# design.net
KiCad netlist of a schematic drawn in Altium Designer
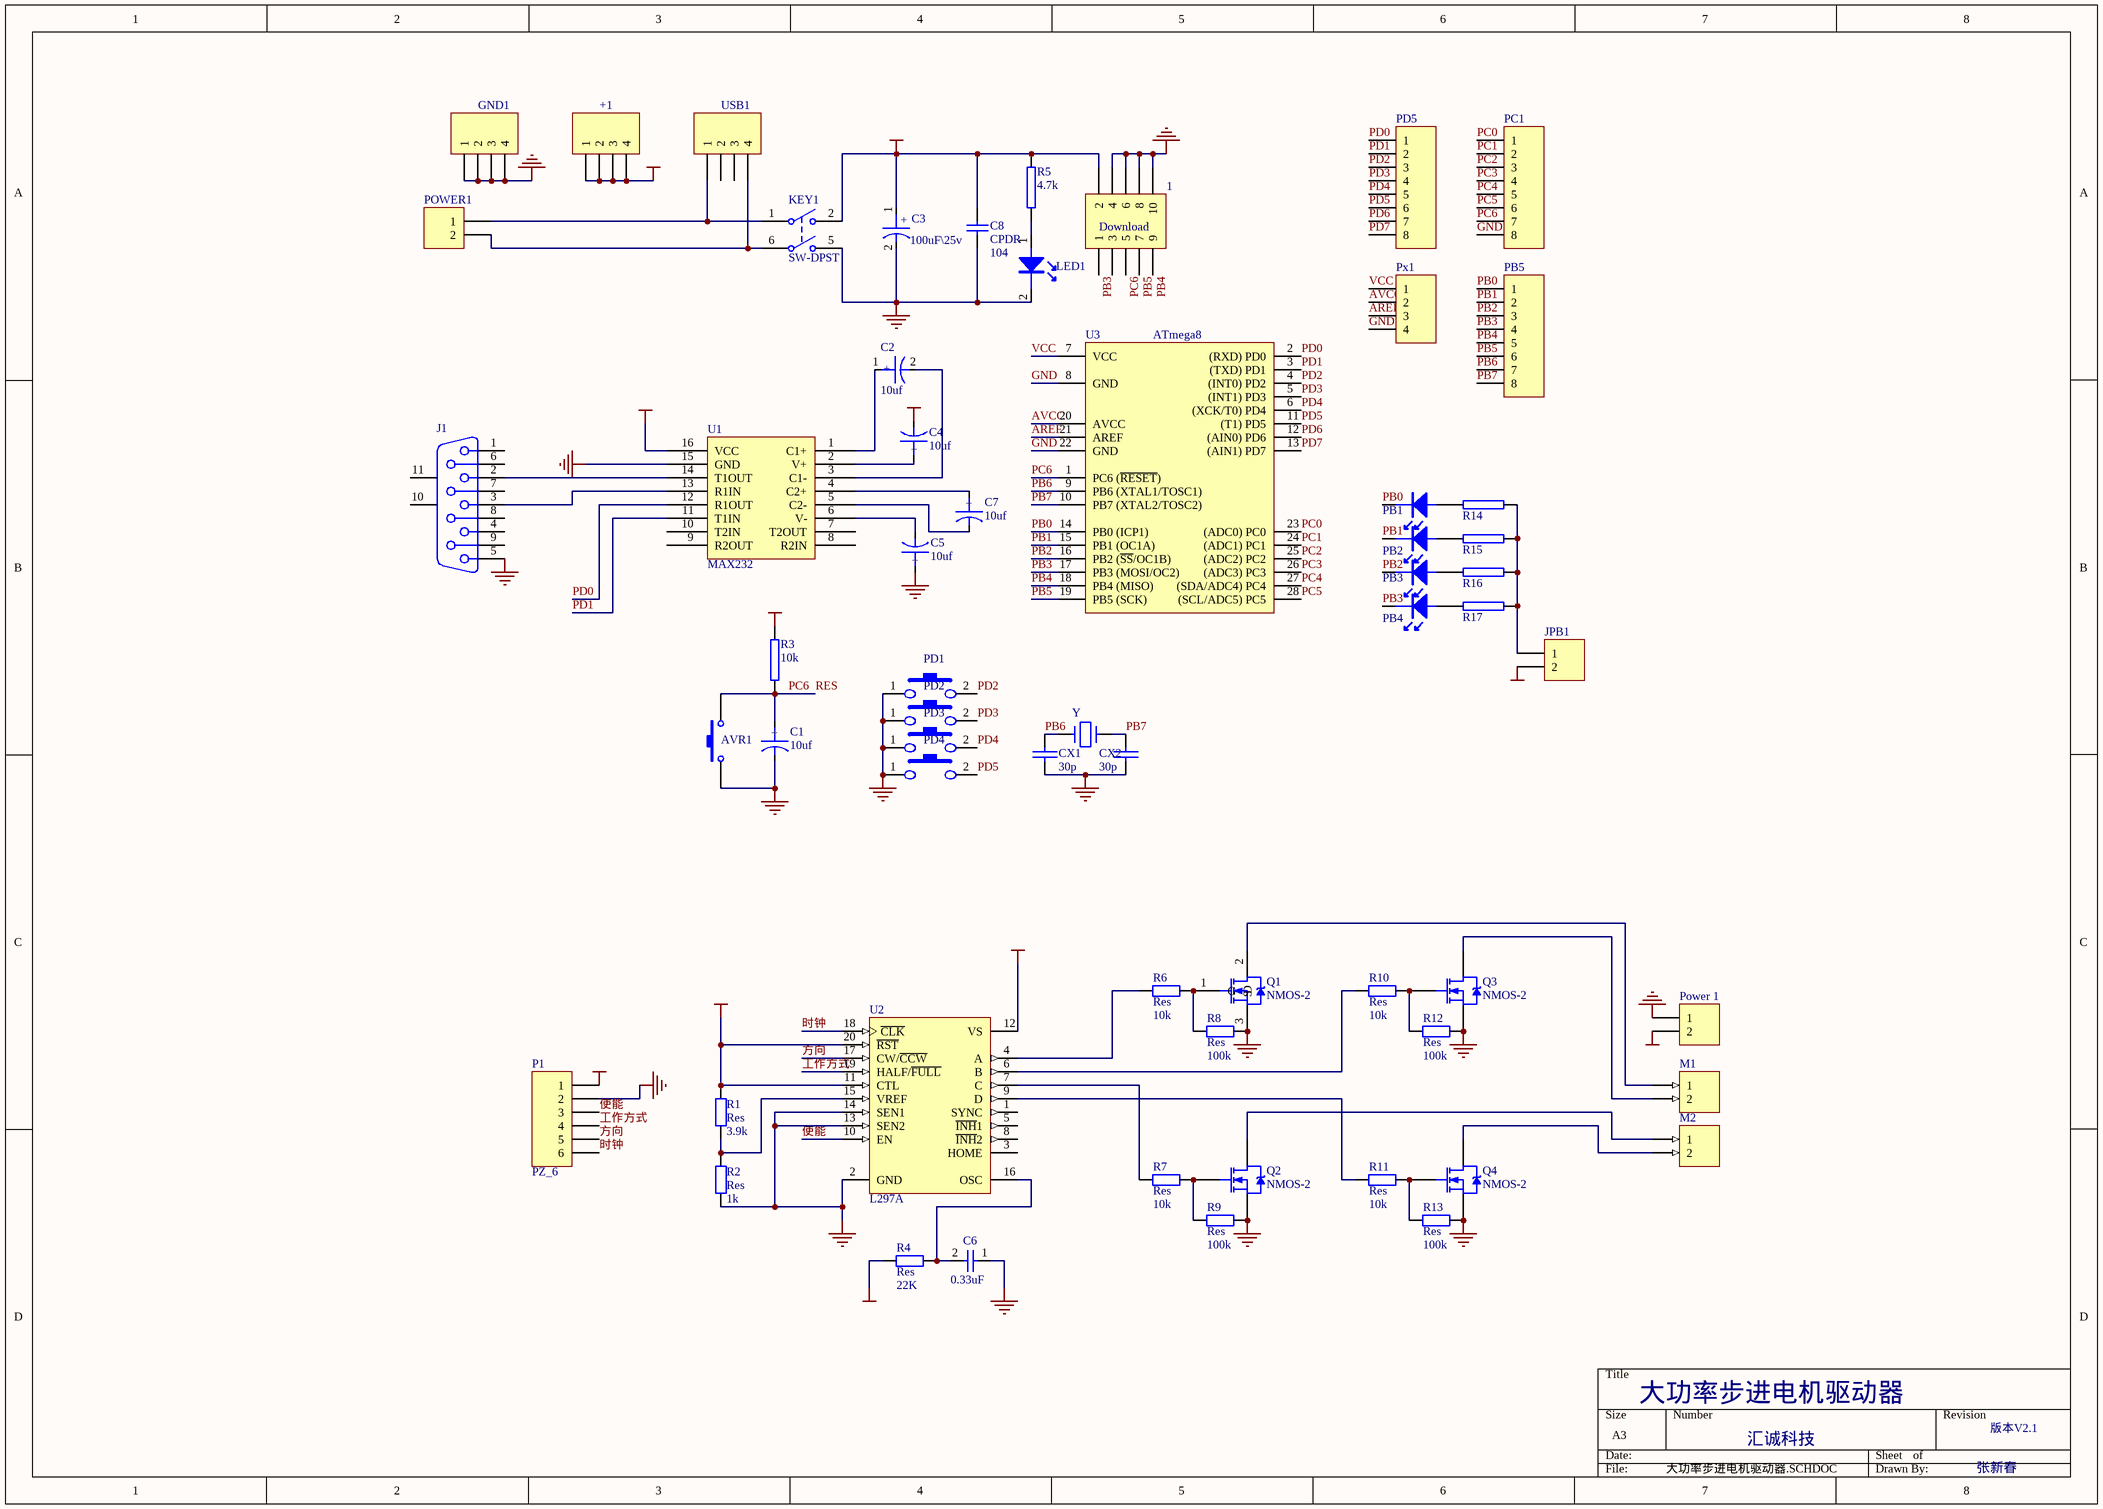
[diagram p0: 大功率步进电机驱动器.SCHDOC]

(export (version "E")
  (design (tool "Eeschema 10.0.6"))
  (components
    (comp (ref "+1")
      (value "~")
      (footprint "HDR1X4")
      (description "Header, 4-Pin")
      (fields (field (name "PUBLISHER") "Altium Limited"))
      (libsource (lib "Miscellaneous Connectors") (part "Header 4"))
    )
    (comp (ref "1")
      (value "Download")
      (footprint "HDR-2x5")
      (description "Header, 5-Pin, Dual row")
      (fields (field (name "PUBLISHER") "Altium Limited"))
      (libsource (lib "Miscellaneous Connectors") (part "Header 5X2"))
    )
    (comp (ref "AVR1")
      (value "~")
      (footprint "an-6*6")
      (description "Switch")
      (fields (field (name "PUBLISHER") "Altium Limited"))
      (libsource (lib "Miscellaneous Devices") (part "SW-PB"))
    )
    (comp (ref "C1")
      (value "10uf")
      (footprint "C-DJ-4")
      (description "Capacitor")
      (libsource (lib "*") (part "CAPACITOR POL"))
    )
    (comp (ref "C2")
      (value "10uf")
      (footprint "C-DJ-4")
      (description "Capacitor")
      (libsource (lib "") (part "CAPACITOR POL_1"))
    )
    (comp (ref "C3")
      (value "100u~{F}25v")
      (footprint "C-DJ-6")
      (description "Capacitor")
      (libsource (lib "OldCow1 (1)") (part "CAPACITOR POL"))
    )
    (comp (ref "C4")
      (value "10uf")
      (footprint "C-DJ-4")
      (description "Capacitor")
      (libsource (lib "*") (part "CAPACITOR POL"))
    )
    (comp (ref "C5")
      (value "10uf")
      (footprint "C-DJ-4")
      (description "Capacitor")
      (libsource (lib "*") (part "CAPACITOR POL"))
    )
    (comp (ref "C6")
      (value "0.33uF")
      (footprint "C-DJ-4")
      (description "Capacitor")
      (fields (field (name "PUBLISHER") "Altium Limited"))
      (libsource (lib "Miscellaneous Devices") (part "Cap"))
    )
    (comp (ref "C7")
      (value "10uf")
      (footprint "C-DJ-4")
      (description "Capacitor")
      (libsource (lib "*") (part "CAPACITOR POL"))
    )
    (comp (ref "C8")
      (value "CPDR")
      (footprint "CPDR")
      (description "瓷片电容")
      (fields (field (name "ALTIUM_VALUE") "104") (field (name "PUBLISHER") "Altium Limited"))
      (libsource (lib "zxcourhc") (part "CPDR"))
    )
    (comp (ref "CX1")
      (value "30p")
      (footprint "HDR1X2")
      (description "Capacitor")
      (libsource (lib "*") (part "CAP"))
    )
    (comp (ref "CX2")
      (value "30p")
      (footprint "HDR1X2")
      (description "Capacitor")
      (libsource (lib "*") (part "CAP"))
    )
    (comp (ref "GND1")
      (value "~")
      (footprint "HDR1X4")
      (description "Header, 4-Pin")
      (fields (field (name "PUBLISHER") "Altium Limited"))
      (libsource (lib "Miscellaneous Connectors") (part "Header 4"))
    )
    (comp (ref "J1")
      (value "D Connector 9")
      (footprint "DSUB1.385-2H9")
      (description "Receptacle Assembly, 9 Position, Right Angle")
      (fields (field (name "PUBLISHER") "Altium Limited"))
      (libsource (lib "Miscellaneous Connectors") (part "D Connector 9"))
    )
    (comp (ref "JPB1")
      (value "~")
      (footprint "HDR1X2")
      (description "Header, 2-Pin")
      (fields (field (name "PUBLISHER") "Altium Limited"))
      (libsource (lib "") (part "Header 2_1"))
    )
    (comp (ref "KEY1")
      (value "SW-DPST")
      (footprint "DPDT-6")
      (description "Double-Pole, Single-Throw Switch")
      (fields (field (name "PUBLISHER") "Altium Limited"))
      (libsource (lib "Miscellaneous Devices") (part "SW-DPST"))
    )
    (comp (ref "LED1") (value "LED") (footprint "LED") (libsource (lib "") (part "LED_1")))
    (comp (ref "M1")
      (value "~")
      (footprint "JK128")
      (description "Header, 2-Pin")
      (fields (field (name "PUBLISHER") "Altium Limited"))
      (libsource (lib "Miscellaneous Connectors") (part "MHDR1X2"))
    )
    (comp (ref "M2")
      (value "~")
      (footprint "JK128")
      (description "Header, 2-Pin")
      (fields (field (name "PUBLISHER") "Altium Limited"))
      (libsource (lib "Miscellaneous Connectors") (part "MHDR1X2"))
    )
    (comp (ref "P1")
      (value "PZ_6")
      (footprint "HDR-6")
      (description "排针——6")
      (fields (field (name "PUBLISHER") "Altium Limited"))
      (libsource (lib "zxcourhc") (part "PZ_6"))
    )
    (comp (ref "PB1") (value "LED") (footprint "HDR1X2") (libsource (lib "OldCow1 (1)") (part "LED")))
    (comp (ref "PB2") (value "LED") (footprint "HDR1X2") (libsource (lib "OldCow1 (1)") (part "LED")))
    (comp (ref "PB3") (value "LED") (footprint "HDR1X2") (libsource (lib "OldCow1 (1)") (part "LED")))
    (comp (ref "PB4") (value "LED") (footprint "HDR1X2") (libsource (lib "OldCow1 (1)") (part "LED")))
    (comp (ref "PB5")
      (value "~")
      (footprint "HDR-8")
      (description "排针——8")
      (fields (field (name "PUBLISHER") "Altium Limited"))
      (libsource (lib "zxcourhc") (part "PZ_8"))
    )
    (comp (ref "PC1")
      (value "~")
      (footprint "HDR-8")
      (description "排针——8")
      (fields (field (name "PUBLISHER") "Altium Limited"))
      (libsource (lib "zxcourhc") (part "PZ_8"))
    )
    (comp (ref "PD1") (value "key1") (footprint "an-6*6") (libsource (lib "OldCow1 (1)") (part "key")))
    (comp (ref "PD2") (value "key2") (footprint "an-6*6") (libsource (lib "OldCow1 (1)") (part "key")))
    (comp (ref "PD3") (value "key3") (footprint "an-6*6") (libsource (lib "OldCow1 (1)") (part "key")))
    (comp (ref "PD4") (value "key4") (footprint "an-6*6") (libsource (lib "OldCow1 (1)") (part "key")))
    (comp (ref "PD5")
      (value "~")
      (footprint "HDR-8")
      (description "排针——8")
      (fields (field (name "PUBLISHER") "Altium Limited"))
      (libsource (lib "zxcourhc") (part "PZ_8"))
    )
    (comp (ref "Power 1")
      (value "~")
      (footprint "JK128")
      (description "Header, 2-Pin")
      (fields (field (name "PUBLISHER") "Altium Limited"))
      (libsource (lib "Miscellaneous Connectors") (part "MHDR1X2"))
    )
    (comp (ref "POWER1")
      (value "~")
      (footprint "JK128")
      (description "Header, 2-Pin")
      (fields (field (name "PUBLISHER") "Altium Limited"))
      (libsource (lib "Miscellaneous Connectors") (part "Header 2"))
    )
    (comp (ref "Px1")
      (value "~")
      (footprint "HDR-4")
      (description "排针——4")
      (fields (field (name "PUBLISHER") "Altium Limited"))
      (libsource (lib "zxcourhc") (part "PZ_4"))
    )
    (comp (ref "Q1")
      (value "NMOS-2")
      (footprint "SFM-T3/A4.7V")
      (description "N-Channel Power MOSFET")
      (fields (field (name "PUBLISHER") "Altium Limited"))
      (libsource (lib "") (part "NMOS-2_1"))
    )
    (comp (ref "Q2")
      (value "NMOS-2")
      (footprint "SFM-T3/A4.7V")
      (description "N-Channel Power MOSFET")
      (fields (field (name "PUBLISHER") "Altium Limited"))
      (libsource (lib "Miscellaneous Devices") (part "NMOS-2"))
    )
    (comp (ref "Q3")
      (value "NMOS-2")
      (footprint "SFM-T3/A4.7V")
      (description "N-Channel Power MOSFET")
      (fields (field (name "PUBLISHER") "Altium Limited"))
      (libsource (lib "Miscellaneous Devices") (part "NMOS-2"))
    )
    (comp (ref "Q4")
      (value "NMOS-2")
      (footprint "SFM-T3/A4.7V")
      (description "N-Channel Power MOSFET")
      (fields (field (name "PUBLISHER") "Altium Limited"))
      (libsource (lib "Miscellaneous Devices") (part "NMOS-2"))
    )
    (comp (ref "R1")
      (value "Res")
      (footprint "zxcourhc:CPDR")
      (description "电阻")
      (fields (field (name "ALTIUM_VALUE") "3.9k") (field (name "PUBLISHER") "Altium Limited"))
      (libsource (lib "") (part "Res_1"))
    )
    (comp (ref "R2")
      (value "Res")
      (footprint "CPDR")
      (description "电阻")
      (fields (field (name "ALTIUM_VALUE") "1k") (field (name "PUBLISHER") "Altium Limited"))
      (libsource (lib "") (part "Res_1"))
    )
    (comp (ref "R3") (value "10k") (footprint "RSE") (libsource (lib "*") (part "RES2")))
    (comp (ref "R4")
      (value "Res")
      (footprint "CPDR")
      (description "电阻")
      (fields (field (name "ALTIUM_VALUE") "22K") (field (name "PUBLISHER") "Altium Limited"))
      (libsource (lib "") (part "Res_2"))
    )
    (comp (ref "R5") (value "4.7k") (footprint "RSE") (libsource (lib "*") (part "RES2")))
    (comp (ref "R6")
      (value "Res")
      (footprint "CPDR")
      (description "电阻")
      (fields (field (name "ALTIUM_VALUE") "10k") (field (name "PUBLISHER") "Altium Limited"))
      (libsource (lib "") (part "Res_2"))
    )
    (comp (ref "R7")
      (value "Res")
      (footprint "CPDR")
      (description "电阻")
      (fields (field (name "ALTIUM_VALUE") "10k") (field (name "PUBLISHER") "Altium Limited"))
      (libsource (lib "") (part "Res_2"))
    )
    (comp (ref "R8")
      (value "Res")
      (footprint "CPDR")
      (description "电阻")
      (fields (field (name "ALTIUM_VALUE") "100k") (field (name "PUBLISHER") "Altium Limited"))
      (libsource (lib "zxcourhc") (part "Res"))
    )
    (comp (ref "R9")
      (value "Res")
      (footprint "CPDR")
      (description "电阻")
      (fields (field (name "ALTIUM_VALUE") "100k") (field (name "PUBLISHER") "Altium Limited"))
      (libsource (lib "zxcourhc") (part "Res"))
    )
    (comp (ref "R10")
      (value "Res")
      (footprint "CPDR")
      (description "电阻")
      (fields (field (name "ALTIUM_VALUE") "10k") (field (name "PUBLISHER") "Altium Limited"))
      (libsource (lib "") (part "Res_2"))
    )
    (comp (ref "R11")
      (value "Res")
      (footprint "CPDR")
      (description "电阻")
      (fields (field (name "ALTIUM_VALUE") "10k") (field (name "PUBLISHER") "Altium Limited"))
      (libsource (lib "") (part "Res_2"))
    )
    (comp (ref "R12")
      (value "Res")
      (footprint "CPDR")
      (description "电阻")
      (fields (field (name "ALTIUM_VALUE") "100k") (field (name "PUBLISHER") "Altium Limited"))
      (libsource (lib "zxcourhc") (part "Res"))
    )
    (comp (ref "R13")
      (value "Res")
      (footprint "CPDR")
      (description "电阻")
      (fields (field (name "ALTIUM_VALUE") "100k") (field (name "PUBLISHER") "Altium Limited"))
      (libsource (lib "zxcourhc") (part "Res"))
    )
    (comp (ref "R14") (value "470") (footprint "RSE") (libsource (lib "*") (part "RES2")))
    (comp (ref "R15") (value "470") (footprint "RSE") (libsource (lib "*") (part "RES2")))
    (comp (ref "R16") (value "470") (footprint "RSE") (libsource (lib "*") (part "RES2")))
    (comp (ref "R17") (value "470") (footprint "RSE") (libsource (lib "*") (part "RES2")))
    (comp (ref "U1") (value "MAX232") (footprint "DIP16") (libsource (lib "*") (part "MAX232")))
    (comp (ref "U2")
      (value "L297A")
      (footprint "DIP20")
      (description "Stepper Motor Controller")
      (fields (field (name "PUBLISHER") "Altium Limited"))
      (libsource (lib "ST Interface Stepper Motor Controller") (part "L297A"))
    )
    (comp (ref "U3")
      (value "ATmega8")
      (footprint "底座DIP-28/引脚7.62mm")
      (description "8 位微处理器/28引脚")
      (fields (field (name "发布者") "磊元工作室"))
      (libsource (lib "MCU") (part "ATmega8-P"))
    )
    (comp (ref "USB1")
      (value "~")
      (footprint "USB-5V")
      (description "Header, 4-Pin")
      (fields (field (name "PUBLISHER") "Altium Limited"))
      (libsource (lib "Miscellaneous Connectors") (part "Header 4"))
    )
    (comp (ref "Y1")
      (value "Y")
      (footprint "JZ_ZC")
      (description "Crystal")
      (libsource (lib "*") (part "CRYSTAL"))
    )
  )
  (nets
    (net (code "1") (name "+5V") (class "Default")
      (node (ref "P1") (pin "1") (pinfunction "1_1") (pintype "passive"))
      (node (ref "R1") (pin "1") (pinfunction "1_1") (pintype "passive"))
      (node (ref "R4") (pin "2") (pinfunction "2_2") (pintype "passive"))
      (node (ref "U2") (pin "11") (pinfunction "CTL_11") (pintype "input"))
      (node (ref "U2") (pin "12") (pinfunction "VS_12") (pintype "power_in"))
      (node (ref "U2") (pin "20") (pinfunction "~{RST}_20") (pintype "input"))
    )
    (net (code "2") (name "/AREF") (class "Default")
      (node (ref "Px1") (pin "3") (pinfunction "3_3") (pintype "passive"))
      (node (ref "U3") (pin "21") (pinfunction "AREF_21") (pintype "passive"))
    )
    (net (code "3") (name "/AVCC") (class "Default")
      (node (ref "Px1") (pin "2") (pinfunction "2_2") (pintype "passive"))
      (node (ref "U3") (pin "20") (pinfunction "AVCC_20") (pintype "passive"))
    )
    (net (code "4") (name "/PB0") (class "Default")
      (node (ref "PB1") (pin "2") (pinfunction "K_2") (pintype "passive"))
      (node (ref "PB5") (pin "1") (pinfunction "1_1") (pintype "passive"))
      (node (ref "U3") (pin "14") (pinfunction "PB0_(ICP1)_14") (pintype "passive"))
    )
    (net (code "5") (name "/PB1") (class "Default")
      (node (ref "PB2") (pin "2") (pinfunction "K_2") (pintype "passive"))
      (node (ref "PB5") (pin "2") (pinfunction "2_2") (pintype "passive"))
      (node (ref "U3") (pin "15") (pinfunction "PB1_(OC1A)_15") (pintype "passive"))
    )
    (net (code "6") (name "/PB2") (class "Default")
      (node (ref "PB3") (pin "2") (pinfunction "K_2") (pintype "passive"))
      (node (ref "PB5") (pin "3") (pinfunction "3_3") (pintype "passive"))
      (node (ref "U3") (pin "16") (pinfunction "PB2_(~{SS}/OC1B)_16") (pintype "passive"))
    )
    (net (code "7") (name "/PB3") (class "Default")
      (node (ref "1") (pin "1") (pinfunction "1_1") (pintype "passive"))
      (node (ref "PB4") (pin "2") (pinfunction "K_2") (pintype "passive"))
      (node (ref "PB5") (pin "4") (pinfunction "4_4") (pintype "passive"))
      (node (ref "U3") (pin "17") (pinfunction "PB3_(MOSI/OC2)_17") (pintype "passive"))
    )
    (net (code "8") (name "/PB4") (class "Default")
      (node (ref "1") (pin "9") (pinfunction "9_9") (pintype "passive"))
      (node (ref "PB5") (pin "5") (pinfunction "5_5") (pintype "passive"))
      (node (ref "U3") (pin "18") (pinfunction "PB4_(MISO)_18") (pintype "passive"))
    )
    (net (code "9") (name "/PB5") (class "Default")
      (node (ref "1") (pin "7") (pinfunction "7_7") (pintype "passive"))
      (node (ref "PB5") (pin "6") (pinfunction "6_6") (pintype "passive"))
      (node (ref "U3") (pin "19") (pinfunction "PB5_(SCK)_19") (pintype "passive"))
    )
    (net (code "10") (name "/PB6") (class "Default")
      (node (ref "CX1") (pin "1") (pinfunction "1_1") (pintype "passive"))
      (node (ref "PB5") (pin "7") (pinfunction "7_7") (pintype "passive"))
      (node (ref "U3") (pin "9") (pinfunction "PB6_(XTAL1/TOSC1)_9") (pintype "passive"))
      (node (ref "Y1") (pin "2") (pinfunction "2_2") (pintype "passive"))
    )
    (net (code "11") (name "/PB7") (class "Default")
      (node (ref "CX2") (pin "1") (pinfunction "1_1") (pintype "passive"))
      (node (ref "PB5") (pin "8") (pinfunction "8_8") (pintype "passive"))
      (node (ref "U3") (pin "10") (pinfunction "PB7_(XTAL2/TOSC2)_10") (pintype "passive"))
      (node (ref "Y1") (pin "1") (pinfunction "1_1") (pintype "passive"))
    )
    (net (code "12") (name "/PC0") (class "Default")
      (node (ref "PC1") (pin "1") (pinfunction "1_1") (pintype "passive"))
      (node (ref "U3") (pin "23") (pinfunction "(ADC0)_PC0_23") (pintype "passive"))
    )
    (net (code "13") (name "/PC1") (class "Default")
      (node (ref "PC1") (pin "2") (pinfunction "2_2") (pintype "passive"))
      (node (ref "U3") (pin "24") (pinfunction "(ADC1)_PC1_24") (pintype "passive"))
    )
    (net (code "14") (name "/PC2") (class "Default")
      (node (ref "PC1") (pin "3") (pinfunction "3_3") (pintype "passive"))
      (node (ref "U3") (pin "25") (pinfunction "(ADC2)_PC2_25") (pintype "passive"))
    )
    (net (code "15") (name "/PC3") (class "Default")
      (node (ref "PC1") (pin "4") (pinfunction "4_4") (pintype "passive"))
      (node (ref "U3") (pin "26") (pinfunction "(ADC3)_PC3_26") (pintype "passive"))
    )
    (net (code "16") (name "/PC4") (class "Default")
      (node (ref "PC1") (pin "5") (pinfunction "5_5") (pintype "passive"))
      (node (ref "U3") (pin "27") (pinfunction "(SDA/ADC4)_PC4_27") (pintype "passive"))
    )
    (net (code "17") (name "/PC5") (class "Default")
      (node (ref "PC1") (pin "6") (pinfunction "6_6") (pintype "passive"))
      (node (ref "U3") (pin "28") (pinfunction "(SCL/ADC5)_PC5_28") (pintype "passive"))
    )
    (net (code "18") (name "/PC6") (class "Default")
      (node (ref "1") (pin "5") (pinfunction "5_5") (pintype "passive"))
      (node (ref "AVR1") (pin "1") (pinfunction "1_1") (pintype "passive"))
      (node (ref "C1") (pin "1") (pinfunction "1_1") (pintype "passive"))
      (node (ref "PC1") (pin "7") (pinfunction "7_7") (pintype "passive"))
      (node (ref "R3") (pin "1") (pinfunction "1_1") (pintype "passive"))
      (node (ref "U3") (pin "1") (pinfunction "PC6_(~{RESET})_1") (pintype "passive"))
    )
    (net (code "19") (name "/PD0") (class "Default")
      (node (ref "PD5") (pin "1") (pinfunction "1_1") (pintype "passive"))
      (node (ref "U1") (pin "12") (pinfunction "R1OUT_12") (pintype "passive"))
      (node (ref "U3") (pin "2") (pinfunction "(RXD)_PD0_2") (pintype "passive"))
    )
    (net (code "20") (name "/PD1") (class "Default")
      (node (ref "PD5") (pin "2") (pinfunction "2_2") (pintype "passive"))
      (node (ref "U1") (pin "11") (pinfunction "T1IN_11") (pintype "passive"))
      (node (ref "U3") (pin "3") (pinfunction "(TXD)_PD1_3") (pintype "passive"))
    )
    (net (code "21") (name "/PD2") (class "Default")
      (node (ref "PD1") (pin "2") (pinfunction "2_2") (pintype "passive"))
      (node (ref "PD5") (pin "3") (pinfunction "3_3") (pintype "passive"))
      (node (ref "U3") (pin "4") (pinfunction "(INT0)_PD2_4") (pintype "passive"))
    )
    (net (code "22") (name "/PD3") (class "Default")
      (node (ref "PD2") (pin "2") (pinfunction "2_2") (pintype "passive"))
      (node (ref "PD5") (pin "4") (pinfunction "4_4") (pintype "passive"))
      (node (ref "U3") (pin "5") (pinfunction "(INT1)_PD3_5") (pintype "passive"))
    )
    (net (code "23") (name "/PD4") (class "Default")
      (node (ref "PD3") (pin "2") (pinfunction "2_2") (pintype "passive"))
      (node (ref "PD5") (pin "5") (pinfunction "5_5") (pintype "passive"))
      (node (ref "U3") (pin "6") (pinfunction "(XCK/T0)_PD4_6") (pintype "passive"))
    )
    (net (code "24") (name "/PD5") (class "Default")
      (node (ref "PD4") (pin "2") (pinfunction "2_2") (pintype "passive"))
      (node (ref "PD5") (pin "6") (pinfunction "6_6") (pintype "passive"))
      (node (ref "U3") (pin "11") (pinfunction "(T1)_PD5_11") (pintype "passive"))
    )
    (net (code "25") (name "/PD6") (class "Default")
      (node (ref "PD5") (pin "7") (pinfunction "7_7") (pintype "passive"))
      (node (ref "U3") (pin "12") (pinfunction "(AIN0)_PD6_12") (pintype "passive"))
    )
    (net (code "26") (name "/PD7") (class "Default")
      (node (ref "PD5") (pin "8") (pinfunction "8_8") (pintype "passive"))
      (node (ref "U3") (pin "13") (pinfunction "(AIN1)_PD7_13") (pintype "passive"))
    )
    (net (code "27") (name "/使能") (class "Default")
      (node (ref "P1") (pin "3") (pinfunction "3_3") (pintype "passive"))
      (node (ref "U2") (pin "10") (pinfunction "EN_10") (pintype "input"))
    )
    (net (code "28") (name "/工作方式") (class "Default")
      (node (ref "P1") (pin "4") (pinfunction "4_4") (pintype "passive"))
      (node (ref "U2") (pin "19") (pinfunction "HALF/~{FULL}_19") (pintype "input"))
    )
    (net (code "29") (name "/方向") (class "Default")
      (node (ref "P1") (pin "5") (pinfunction "5_5") (pintype "passive"))
      (node (ref "U2") (pin "17") (pinfunction "CW/~{CCW}_17") (pintype "input"))
    )
    (net (code "30") (name "/时钟") (class "Default")
      (node (ref "P1") (pin "6") (pinfunction "6_6") (pintype "passive"))
      (node (ref "U2") (pin "18") (pinfunction "~{CLK}_18") (pintype "input"))
    )
    (net (code "31") (name "GND") (class "Default")
      (node (ref "1") (pin "10") (pinfunction "10_10") (pintype "passive"))
      (node (ref "1") (pin "4") (pinfunction "4_4") (pintype "passive"))
      (node (ref "1") (pin "6") (pinfunction "6_6") (pintype "passive"))
      (node (ref "1") (pin "8") (pinfunction "8_8") (pintype "passive"))
      (node (ref "AVR1") (pin "2") (pinfunction "2_2") (pintype "passive"))
      (node (ref "C1") (pin "2") (pinfunction "2_2") (pintype "passive"))
      (node (ref "C3") (pin "2") (pinfunction "2_2") (pintype "passive"))
      (node (ref "C5") (pin "1") (pinfunction "1_1") (pintype "passive"))
      (node (ref "C8") (pin "1") (pinfunction "1_1") (pintype "passive"))
      (node (ref "CX1") (pin "2") (pinfunction "2_2") (pintype "passive"))
      (node (ref "CX2") (pin "2") (pinfunction "2_2") (pintype "passive"))
      (node (ref "GND1") (pin "1") (pinfunction "1_1") (pintype "passive"))
      (node (ref "GND1") (pin "2") (pinfunction "2_2") (pintype "passive"))
      (node (ref "GND1") (pin "3") (pinfunction "3_3") (pintype "passive"))
      (node (ref "GND1") (pin "4") (pinfunction "4_4") (pintype "passive"))
      (node (ref "J1") (pin "5") (pinfunction "5_5") (pintype "passive"))
      (node (ref "KEY1") (pin "5") (pinfunction "NO2_5") (pintype "passive"))
      (node (ref "LED1") (pin "2") (pinfunction "K_2") (pintype "passive"))
      (node (ref "P1") (pin "2") (pinfunction "2_2") (pintype "passive"))
      (node (ref "PC1") (pin "8") (pinfunction "8_8") (pintype "passive"))
      (node (ref "PD1") (pin "1") (pinfunction "1_1") (pintype "passive"))
      (node (ref "PD2") (pin "1") (pinfunction "1_1") (pintype "passive"))
      (node (ref "PD3") (pin "1") (pinfunction "1_1") (pintype "passive"))
      (node (ref "PD4") (pin "1") (pinfunction "1_1") (pintype "passive"))
      (node (ref "Power 1") (pin "1") (pinfunction "1_1") (pintype "power_in"))
      (node (ref "Px1") (pin "4") (pinfunction "4_4") (pintype "passive"))
      (node (ref "Q1") (pin "3") (pinfunction "S_3") (pintype "passive"))
      (node (ref "Q2") (pin "3") (pinfunction "S_3") (pintype "passive"))
      (node (ref "Q3") (pin "3") (pinfunction "S_3") (pintype "passive"))
      (node (ref "Q4") (pin "3") (pinfunction "S_3") (pintype "passive"))
      (node (ref "R12") (pin "2") (pinfunction "2_2") (pintype "passive"))
      (node (ref "R13") (pin "2") (pinfunction "2_2") (pintype "passive"))
      (node (ref "R2") (pin "2") (pinfunction "2_2") (pintype "passive"))
      (node (ref "R8") (pin "2") (pinfunction "2_2") (pintype "passive"))
      (node (ref "R9") (pin "2") (pinfunction "2_2") (pintype "passive"))
      (node (ref "U1") (pin "15") (pinfunction "GND_15") (pintype "passive"))
      (node (ref "U2") (pin "13") (pinfunction "SEN2_13") (pintype "input"))
      (node (ref "U2") (pin "14") (pinfunction "SEN1_14") (pintype "input"))
      (node (ref "U2") (pin "2") (pinfunction "GND_2") (pintype "power_in"))
      (node (ref "U3") (pin "22") (pinfunction "GND_22") (pintype "passive"))
      (node (ref "U3") (pin "8") (pinfunction "GND_8") (pintype "passive"))
    )
    (net (code "32") (name "GND-12") (class "Default")
      (node (ref "C6") (pin "1") (pinfunction "1_1") (pintype "passive"))
    )
    (net (code "33") (name "Net-(JPB1-Pad1)") (class "Default")
      (node (ref "JPB1") (pin "1") (pinfunction "1_1") (pintype "passive"))
      (node (ref "R14") (pin "1") (pinfunction "1_1") (pintype "passive"))
      (node (ref "R15") (pin "1") (pinfunction "1_1") (pintype "passive"))
      (node (ref "R16") (pin "1") (pinfunction "1_1") (pintype "passive"))
      (node (ref "R17") (pin "1") (pinfunction "1_1") (pintype "passive"))
    )
    (net (code "34") (name "Net-(KEY1-COMMON1)") (class "Default")
      (node (ref "KEY1") (pin "1") (pinfunction "COMMON1_1") (pintype "passive"))
      (node (ref "POWER1") (pin "1") (pinfunction "1_1") (pintype "passive"))
      (node (ref "USB1") (pin "1") (pinfunction "1_1") (pintype "passive"))
    )
    (net (code "35") (name "Net-(KEY1-COMMON2)") (class "Default")
      (node (ref "KEY1") (pin "6") (pinfunction "COMMON2_6") (pintype "passive"))
      (node (ref "POWER1") (pin "2") (pinfunction "2_2") (pintype "passive"))
      (node (ref "USB1") (pin "4") (pinfunction "4_4") (pintype "passive"))
    )
    (net (code "36") (name "Net-(LED1-A)") (class "Default")
      (node (ref "LED1") (pin "1") (pinfunction "A_1") (pintype "passive"))
      (node (ref "R5") (pin "2") (pinfunction "2_2") (pintype "passive"))
    )
    (net (code "37") (name "Net-(PB1-A)") (class "Default")
      (node (ref "PB1") (pin "1") (pinfunction "A_1") (pintype "passive"))
      (node (ref "R14") (pin "2") (pinfunction "2_2") (pintype "passive"))
    )
    (net (code "38") (name "Net-(PB2-A)") (class "Default")
      (node (ref "PB2") (pin "1") (pinfunction "A_1") (pintype "passive"))
      (node (ref "R15") (pin "2") (pinfunction "2_2") (pintype "passive"))
    )
    (net (code "39") (name "Net-(PB3-A)") (class "Default")
      (node (ref "PB3") (pin "1") (pinfunction "A_1") (pintype "passive"))
      (node (ref "R16") (pin "2") (pinfunction "2_2") (pintype "passive"))
    )
    (net (code "40") (name "Net-(PB4-A)") (class "Default")
      (node (ref "PB4") (pin "1") (pinfunction "A_1") (pintype "passive"))
      (node (ref "R17") (pin "2") (pinfunction "2_2") (pintype "passive"))
    )
    (net (code "41") (name "Net-(Q1-D)") (class "Default")
      (node (ref "M1") (pin "1") (pinfunction "1_1") (pintype "power_in"))
      (node (ref "Q1") (pin "2") (pinfunction "D_2") (pintype "passive"))
    )
    (net (code "42") (name "Net-(Q1-G)") (class "Default")
      (node (ref "Q1") (pin "1") (pinfunction "G_1") (pintype "passive"))
      (node (ref "R6") (pin "1") (pinfunction "1_1") (pintype "passive"))
      (node (ref "R8") (pin "1") (pinfunction "1_1") (pintype "passive"))
    )
    (net (code "43") (name "Net-(Q2-D)") (class "Default")
      (node (ref "M2") (pin "1") (pinfunction "1_1") (pintype "power_in"))
      (node (ref "Q2") (pin "2") (pinfunction "D_2") (pintype "passive"))
    )
    (net (code "44") (name "Net-(Q2-G)") (class "Default")
      (node (ref "Q2") (pin "1") (pinfunction "G_1") (pintype "passive"))
      (node (ref "R7") (pin "1") (pinfunction "1_1") (pintype "passive"))
      (node (ref "R9") (pin "1") (pinfunction "1_1") (pintype "passive"))
    )
    (net (code "45") (name "Net-(Q3-D)") (class "Default")
      (node (ref "M1") (pin "2") (pinfunction "2_2") (pintype "power_in"))
      (node (ref "Q3") (pin "2") (pinfunction "D_2") (pintype "passive"))
    )
    (net (code "46") (name "Net-(Q3-G)") (class "Default")
      (node (ref "Q3") (pin "1") (pinfunction "G_1") (pintype "passive"))
      (node (ref "R10") (pin "1") (pinfunction "1_1") (pintype "passive"))
      (node (ref "R12") (pin "1") (pinfunction "1_1") (pintype "passive"))
    )
    (net (code "47") (name "Net-(Q4-D)") (class "Default")
      (node (ref "M2") (pin "2") (pinfunction "2_2") (pintype "power_in"))
      (node (ref "Q4") (pin "2") (pinfunction "D_2") (pintype "passive"))
    )
    (net (code "48") (name "Net-(Q4-G)") (class "Default")
      (node (ref "Q4") (pin "1") (pinfunction "G_1") (pintype "passive"))
      (node (ref "R11") (pin "1") (pinfunction "1_1") (pintype "passive"))
      (node (ref "R13") (pin "1") (pinfunction "1_1") (pintype "passive"))
    )
    (net (code "49") (name "Net-(U1-C1+)") (class "Default")
      (node (ref "C2") (pin "1") (pinfunction "1_1") (pintype "passive"))
      (node (ref "U1") (pin "1") (pinfunction "C1+_1") (pintype "passive"))
    )
    (net (code "50") (name "Net-(U1-C1-)") (class "Default")
      (node (ref "C2") (pin "2") (pinfunction "2_2") (pintype "passive"))
      (node (ref "U1") (pin "3") (pinfunction "C1-_3") (pintype "passive"))
    )
    (net (code "51") (name "Net-(U1-C2+)") (class "Default")
      (node (ref "C7") (pin "1") (pinfunction "1_1") (pintype "passive"))
      (node (ref "U1") (pin "4") (pinfunction "C2+_4") (pintype "passive"))
    )
    (net (code "52") (name "Net-(U1-C2-)") (class "Default")
      (node (ref "C7") (pin "2") (pinfunction "2_2") (pintype "passive"))
      (node (ref "U1") (pin "5") (pinfunction "C2-_5") (pintype "passive"))
    )
    (net (code "53") (name "Net-(U1-R1IN)") (class "Default")
      (node (ref "J1") (pin "3") (pinfunction "3_3") (pintype "passive"))
      (node (ref "U1") (pin "13") (pinfunction "R1IN_13") (pintype "passive"))
    )
    (net (code "54") (name "Net-(U1-T1OUT)") (class "Default")
      (node (ref "J1") (pin "2") (pinfunction "2_2") (pintype "passive"))
      (node (ref "U1") (pin "14") (pinfunction "T1OUT_14") (pintype "passive"))
    )
    (net (code "55") (name "Net-(U1-V+)") (class "Default")
      (node (ref "C4") (pin "1") (pinfunction "1_1") (pintype "passive"))
      (node (ref "U1") (pin "2") (pinfunction "V+_2") (pintype "passive"))
    )
    (net (code "56") (name "Net-(U1-V-)") (class "Default")
      (node (ref "C5") (pin "2") (pinfunction "2_2") (pintype "passive"))
      (node (ref "U1") (pin "6") (pinfunction "V-_6") (pintype "passive"))
    )
    (net (code "57") (name "Net-(U2-A)") (class "Default")
      (node (ref "R6") (pin "2") (pinfunction "2_2") (pintype "passive"))
      (node (ref "U2") (pin "4") (pinfunction "A_4") (pintype "output"))
    )
    (net (code "58") (name "Net-(U2-B)") (class "Default")
      (node (ref "R10") (pin "2") (pinfunction "2_2") (pintype "passive"))
      (node (ref "U2") (pin "6") (pinfunction "B_6") (pintype "output"))
    )
    (net (code "59") (name "Net-(U2-C)") (class "Default")
      (node (ref "R7") (pin "2") (pinfunction "2_2") (pintype "passive"))
      (node (ref "U2") (pin "7") (pinfunction "C_7") (pintype "output"))
    )
    (net (code "60") (name "Net-(U2-D)") (class "Default")
      (node (ref "R11") (pin "2") (pinfunction "2_2") (pintype "passive"))
      (node (ref "U2") (pin "9") (pinfunction "D_9") (pintype "output"))
    )
    (net (code "61") (name "Net-(U2-OSC)") (class "Default")
      (node (ref "C6") (pin "2") (pinfunction "2_2") (pintype "passive"))
      (node (ref "R4") (pin "1") (pinfunction "1_1") (pintype "passive"))
      (node (ref "U2") (pin "16") (pinfunction "OSC_16") (pintype "passive"))
    )
    (net (code "62") (name "Net-(U2-VREF)") (class "Default")
      (node (ref "R1") (pin "2") (pinfunction "2_2") (pintype "passive"))
      (node (ref "R2") (pin "1") (pinfunction "1_1") (pintype "passive"))
      (node (ref "U2") (pin "15") (pinfunction "VREF_15") (pintype "input"))
    )
    (net (code "63") (name "VCC") (class "Default")
      (node (ref "+1") (pin "1") (pinfunction "1_1") (pintype "passive"))
      (node (ref "+1") (pin "2") (pinfunction "2_2") (pintype "passive"))
      (node (ref "+1") (pin "3") (pinfunction "3_3") (pintype "passive"))
      (node (ref "+1") (pin "4") (pinfunction "4_4") (pintype "passive"))
      (node (ref "1") (pin "2") (pinfunction "2_2") (pintype "passive"))
      (node (ref "C3") (pin "1") (pinfunction "1_1") (pintype "passive"))
      (node (ref "C4") (pin "2") (pinfunction "2_2") (pintype "passive"))
      (node (ref "C8") (pin "2") (pinfunction "2_2") (pintype "passive"))
      (node (ref "JPB1") (pin "2") (pinfunction "2_2") (pintype "passive"))
      (node (ref "KEY1") (pin "2") (pinfunction "NO1_2") (pintype "passive"))
      (node (ref "Power 1") (pin "2") (pinfunction "2_2") (pintype "power_in"))
      (node (ref "Px1") (pin "1") (pinfunction "1_1") (pintype "passive"))
      (node (ref "R3") (pin "2") (pinfunction "2_2") (pintype "passive"))
      (node (ref "R5") (pin "1") (pinfunction "1_1") (pintype "passive"))
      (node (ref "U1") (pin "16") (pinfunction "VCC_16") (pintype "passive"))
      (node (ref "U3") (pin "7") (pinfunction "VCC_7") (pintype "passive"))
    )
    (net (code "64") (name "unconnected-(1-Pad3)") (class "Default")
      (node (ref "1") (pin "3") (pinfunction "3_3") (pintype "passive"))
    )
    (net (code "65") (name "unconnected-(J1-MH1-Pad10)") (class "Default")
      (node (ref "J1") (pin "10") (pinfunction "MH1_10") (pintype "passive"))
    )
    (net (code "66") (name "unconnected-(J1-MH2-Pad11)") (class "Default")
      (node (ref "J1") (pin "11") (pinfunction "MH2_11") (pintype "passive"))
    )
    (net (code "67") (name "unconnected-(J1-Pad1)") (class "Default")
      (node (ref "J1") (pin "1") (pinfunction "1_1") (pintype "passive"))
    )
    (net (code "68") (name "unconnected-(J1-Pad4)") (class "Default")
      (node (ref "J1") (pin "4") (pinfunction "4_4") (pintype "passive"))
    )
    (net (code "69") (name "unconnected-(J1-Pad6)") (class "Default")
      (node (ref "J1") (pin "6") (pinfunction "6_6") (pintype "passive"))
    )
    (net (code "70") (name "unconnected-(J1-Pad7)") (class "Default")
      (node (ref "J1") (pin "7") (pinfunction "7_7") (pintype "passive"))
    )
    (net (code "71") (name "unconnected-(J1-Pad8)") (class "Default")
      (node (ref "J1") (pin "8") (pinfunction "8_8") (pintype "passive"))
    )
    (net (code "72") (name "unconnected-(J1-Pad9)") (class "Default")
      (node (ref "J1") (pin "9") (pinfunction "9_9") (pintype "passive"))
    )
    (net (code "73") (name "unconnected-(U1-R2IN-Pad8)") (class "Default")
      (node (ref "U1") (pin "8") (pinfunction "R2IN_8") (pintype "passive"))
    )
    (net (code "74") (name "unconnected-(U1-R2OUT-Pad9)") (class "Default")
      (node (ref "U1") (pin "9") (pinfunction "R2OUT_9") (pintype "passive"))
    )
    (net (code "75") (name "unconnected-(U1-T2IN-Pad10)") (class "Default")
      (node (ref "U1") (pin "10") (pinfunction "T2IN_10") (pintype "passive"))
    )
    (net (code "76") (name "unconnected-(U1-T2OUT-Pad7)") (class "Default")
      (node (ref "U1") (pin "7") (pinfunction "T2OUT_7") (pintype "passive"))
    )
    (net (code "77") (name "unconnected-(U2-HOME-Pad3)") (class "Default")
      (node (ref "U2") (pin "3") (pinfunction "HOME_3") (pintype "open_collector"))
    )
    (net (code "78") (name "unconnected-(U2-SYNC-Pad1)") (class "Default")
      (node (ref "U2") (pin "1") (pinfunction "SYNC_1") (pintype "output"))
    )
    (net (code "79") (name "unconnected-(U2-~{INH}1-Pad5)") (class "Default")
      (node (ref "U2") (pin "5") (pinfunction "~{INH}1_5") (pintype "output"))
    )
    (net (code "80") (name "unconnected-(U2-~{INH}2-Pad8)") (class "Default")
      (node (ref "U2") (pin "8") (pinfunction "~{INH}2_8") (pintype "output"))
    )
    (net (code "81") (name "unconnected-(USB1-Pad2)") (class "Default")
      (node (ref "USB1") (pin "2") (pinfunction "2_2") (pintype "passive"))
    )
    (net (code "82") (name "unconnected-(USB1-Pad3)") (class "Default")
      (node (ref "USB1") (pin "3") (pinfunction "3_3") (pintype "passive"))
    )
  )
)
